# DragonUSBHost.net
KiCad netlist of a schematic drawn in EAGLE
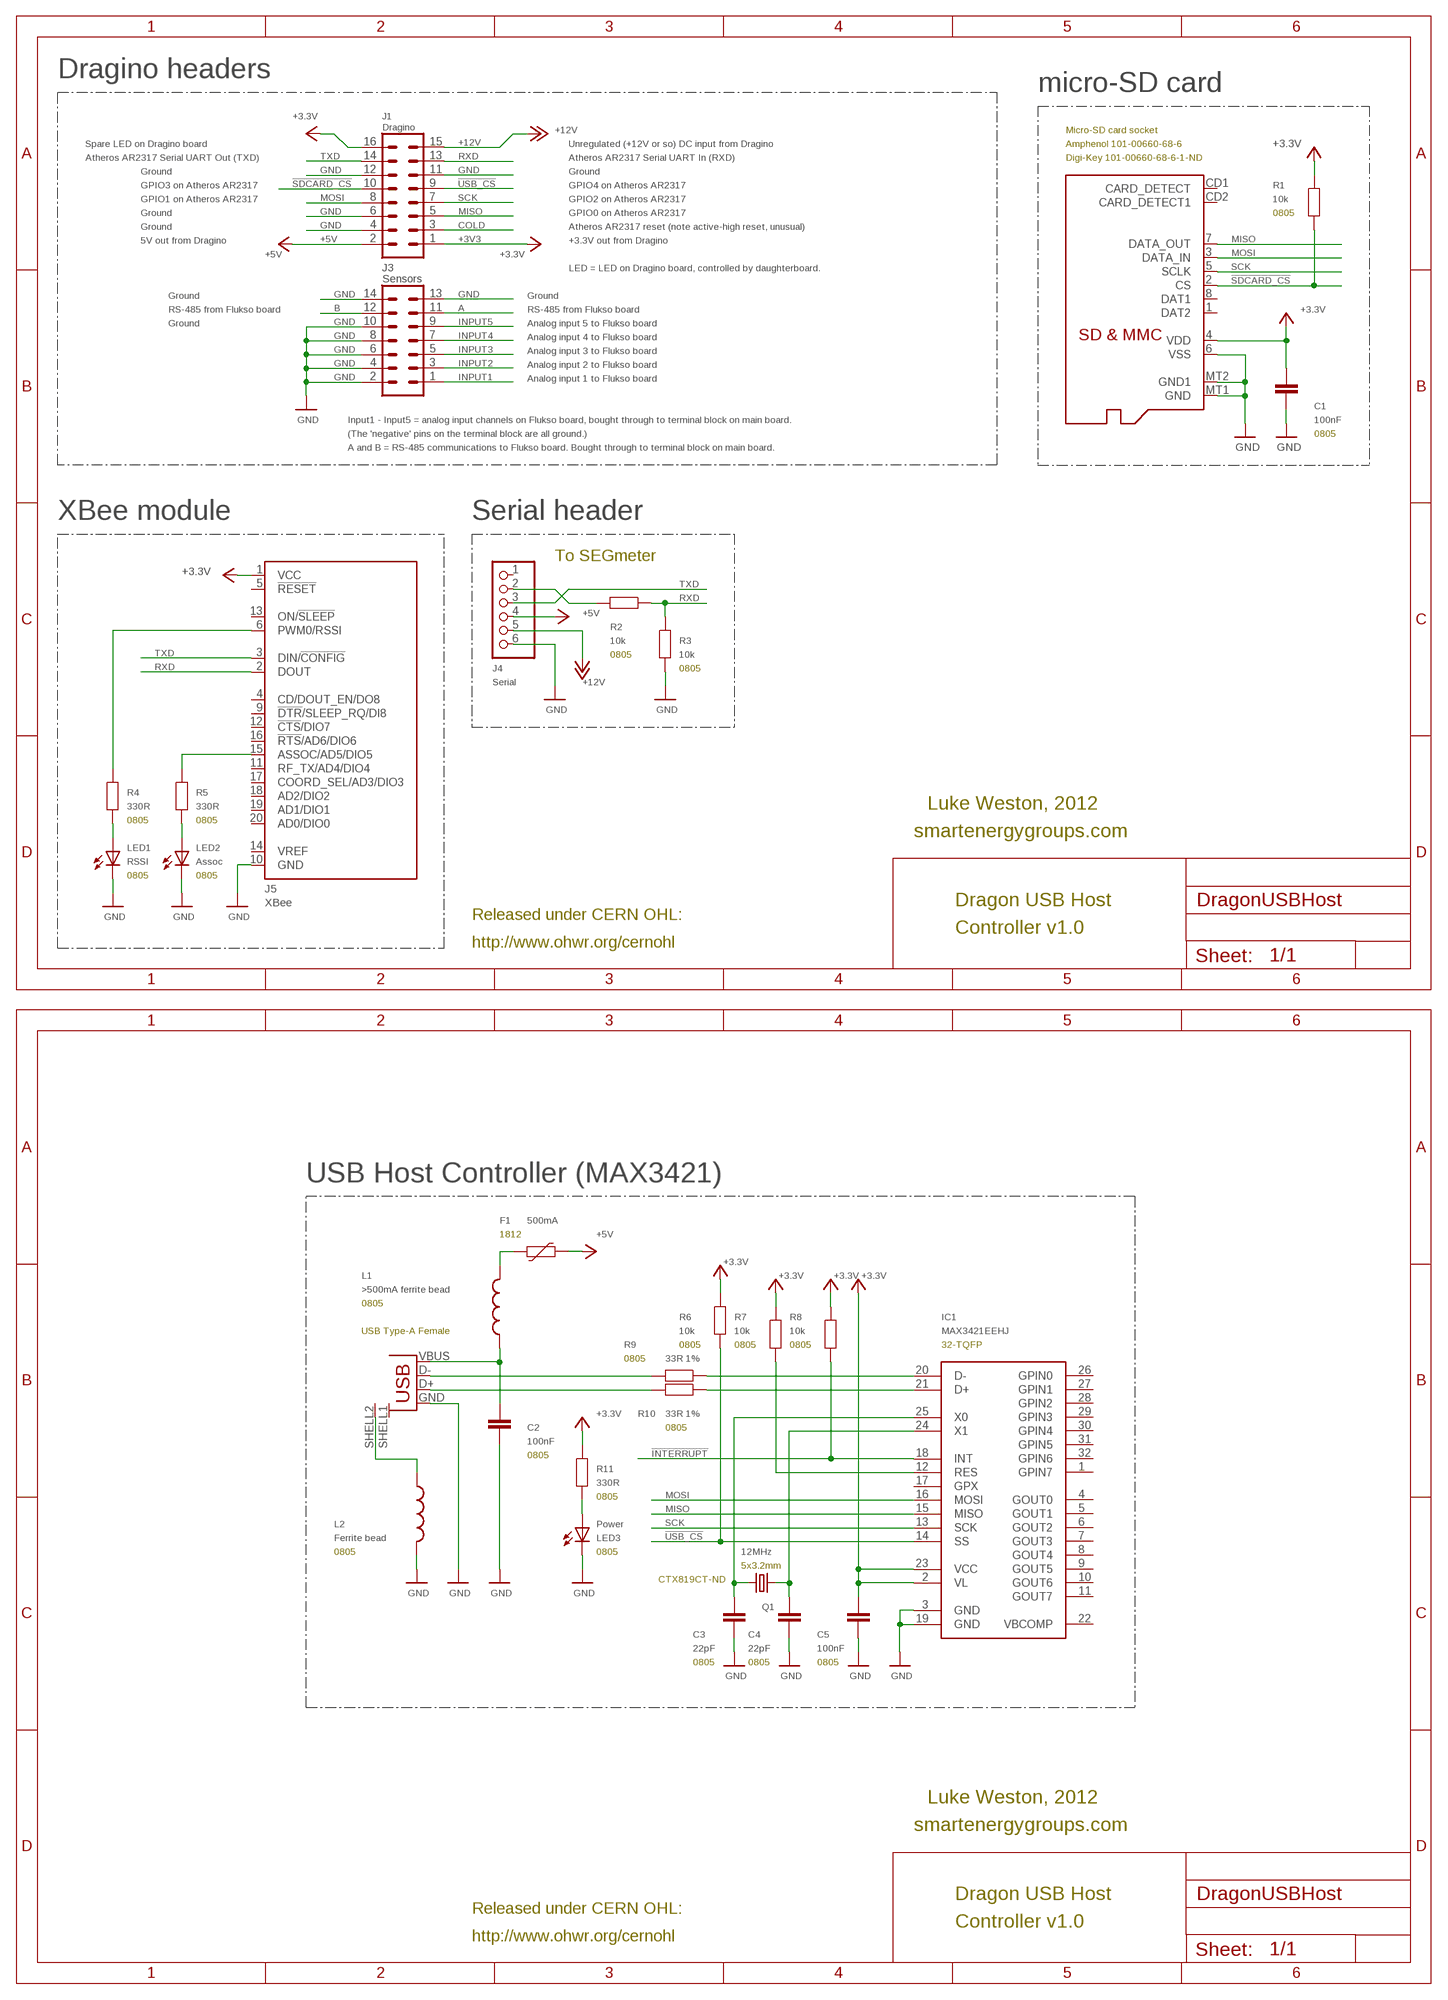
[diagram p0: schematic, sheet 1]

(export (version "E")
  (design (tool "Eeschema 10.0.6"))
  (components
    (comp (ref "C1")
      (value "100nF")
      (footprint "eagle-import:0805")
      (libsource (lib "eagle-import") (part "CAP0805"))
    )
    (comp (ref "C2")
      (value "100nF")
      (footprint "eagle-import:0805")
      (libsource (lib "eagle-import") (part "CAP0805"))
    )
    (comp (ref "C3")
      (value "22pF")
      (footprint "eagle-import:0805")
      (libsource (lib "eagle-import") (part "CAP0805"))
    )
    (comp (ref "C4")
      (value "22pF")
      (footprint "eagle-import:0805")
      (libsource (lib "eagle-import") (part "CAP0805"))
    )
    (comp (ref "C5")
      (value "100nF")
      (footprint "eagle-import:0805")
      (libsource (lib "eagle-import") (part "CAP0805"))
    )
    (comp (ref "F1")
      (value "500mA")
      (footprint "eagle-import:1812")
      (libsource (lib "eagle-import") (part "PTC"))
    )
    (comp (ref "IC1")
      (value "MAX3421EEHJ")
      (footprint "eagle-import:TQFP32-5MM")
      (libsource (lib "eagle-import") (part "MAX3421ESMD"))
    )
    (comp (ref "J1")
      (value "Dragino")
      (footprint "eagle-import:MA08-2")
      (libsource (lib "eagle-import") (part "MA08-2"))
    )
    (comp (ref "J2")
      (value "MICROSD")
      (footprint "eagle-import:MICROSD")
      (libsource (lib "eagle-import") (part "MICROSD"))
    )
    (comp (ref "J3")
      (value "Sensors")
      (footprint "eagle-import:MA07-2")
      (libsource (lib "eagle-import") (part "MA07-2"))
    )
    (comp (ref "J4")
      (value "Serial")
      (footprint "eagle-import:1X06")
      (libsource (lib "eagle-import") (part "PINHD-1X6"))
    )
    (comp (ref "J5")
      (value "XBee")
      (footprint "eagle-import:XBEE-PRO")
      (fields (field (name "MPN") "XBP24-AWI-001"))
      (libsource (lib "eagle-import") (part "XBEE-PRO"))
    )
    (comp (ref "L1")
      (value ">500mA ferrite bead")
      (footprint "eagle-import:0805-LARGE")
      (libsource (lib "eagle-import") (part "INDUCTOR0805-LARGE"))
    )
    (comp (ref "L2")
      (value "Ferrite bead")
      (footprint "eagle-import:0805-LARGE")
      (libsource (lib "eagle-import") (part "INDUCTOR0805-LARGE"))
    )
    (comp (ref "LED1")
      (value "RSSI")
      (footprint "eagle-import:LED-0805")
      (libsource (lib "eagle-import") (part "LED0805"))
    )
    (comp (ref "LED2")
      (value "Assoc")
      (footprint "eagle-import:LED-0805")
      (libsource (lib "eagle-import") (part "LED0805"))
    )
    (comp (ref "LED3")
      (value "Power")
      (footprint "eagle-import:LED-0805")
      (libsource (lib "eagle-import") (part "LED0805"))
    )
    (comp (ref "P1")
      (value "USB_")
      (footprint "eagle-import:USB-A-S-SILK-FEMALE")
      (libsource (lib "eagle-import") (part "USB_"))
    )
    (comp (ref "Q1")
      (value "12MHz")
      (footprint "eagle-import:CRYSTAL-SMD-5X3")
      (libsource (lib "eagle-import") (part "CRYSTAL5X3"))
    )
    (comp (ref "R1")
      (value "10k")
      (footprint "eagle-import:0805")
      (libsource (lib "eagle-import") (part "RESISTOR0805"))
    )
    (comp (ref "R2")
      (value "10k")
      (footprint "eagle-import:0805")
      (libsource (lib "eagle-import") (part "RESISTOR0805"))
    )
    (comp (ref "R3")
      (value "10k")
      (footprint "eagle-import:0805")
      (libsource (lib "eagle-import") (part "RESISTOR0805"))
    )
    (comp (ref "R4")
      (value "330R")
      (footprint "eagle-import:0805")
      (libsource (lib "eagle-import") (part "RESISTOR0805"))
    )
    (comp (ref "R5")
      (value "330R")
      (footprint "eagle-import:0805")
      (libsource (lib "eagle-import") (part "RESISTOR0805"))
    )
    (comp (ref "R6")
      (value "10k")
      (footprint "eagle-import:0805")
      (libsource (lib "eagle-import") (part "RESISTOR0805"))
    )
    (comp (ref "R7")
      (value "10k")
      (footprint "eagle-import:0805")
      (libsource (lib "eagle-import") (part "RESISTOR0805"))
    )
    (comp (ref "R8")
      (value "10k")
      (footprint "eagle-import:0805")
      (libsource (lib "eagle-import") (part "RESISTOR0805"))
    )
    (comp (ref "R9")
      (value "33R 1%")
      (footprint "eagle-import:0805")
      (libsource (lib "eagle-import") (part "RESISTOR0805"))
    )
    (comp (ref "R10")
      (value "33R 1%")
      (footprint "eagle-import:0805")
      (libsource (lib "eagle-import") (part "RESISTOR0805"))
    )
    (comp (ref "R11")
      (value "330R")
      (footprint "eagle-import:0805")
      (libsource (lib "eagle-import") (part "RESISTOR0805"))
    )
  )
  (nets
    (net (code "1") (name "+3.3V") (class "Default")
      (node (ref "C1") (pin "1") (pinfunction "1_1") (pintype "passive"))
      (node (ref "C5") (pin "1") (pinfunction "1_1") (pintype "passive"))
      (node (ref "IC1") (pin "2") (pinfunction "VL_2") (pintype "bidirectional"))
      (node (ref "IC1") (pin "23") (pinfunction "VCC_23") (pintype "bidirectional"))
      (node (ref "J1") (pin "1") (pinfunction "1_1") (pintype "passive"))
      (node (ref "J1") (pin "16") (pinfunction "16_16") (pintype "passive"))
      (node (ref "J2") (pin "4") (pinfunction "VDD_4") (pintype "power_in"))
      (node (ref "J5") (pin "1") (pinfunction "VCC_1") (pintype "power_in"))
      (node (ref "R1") (pin "2") (pinfunction "2_2") (pintype "passive"))
      (node (ref "R11") (pin "2") (pinfunction "2_2") (pintype "passive"))
      (node (ref "R6") (pin "2") (pinfunction "2_2") (pintype "passive"))
      (node (ref "R7") (pin "2") (pinfunction "2_2") (pintype "passive"))
      (node (ref "R8") (pin "2") (pinfunction "2_2") (pintype "passive"))
    )
    (net (code "2") (name "+5V") (class "Default")
      (node (ref "F1") (pin "2") (pinfunction "P$2_2") (pintype "bidirectional"))
      (node (ref "J1") (pin "2") (pinfunction "2_2") (pintype "passive"))
      (node (ref "J4") (pin "4") (pinfunction "4_4") (pintype "passive"))
    )
    (net (code "3") (name "+12V") (class "Default")
      (node (ref "J1") (pin "15") (pinfunction "15_15") (pintype "passive"))
      (node (ref "J4") (pin "5") (pinfunction "5_5") (pintype "passive"))
    )
    (net (code "4") (name "/A") (class "Default")
      (node (ref "J3") (pin "11") (pinfunction "11_11") (pintype "passive"))
    )
    (net (code "5") (name "/B") (class "Default")
      (node (ref "J3") (pin "12") (pinfunction "12_12") (pintype "passive"))
    )
    (net (code "6") (name "/COLD") (class "Default")
      (node (ref "J1") (pin "3") (pinfunction "3_3") (pintype "passive"))
    )
    (net (code "7") (name "/INPUT1") (class "Default")
      (node (ref "J3") (pin "1") (pinfunction "1_1") (pintype "passive"))
    )
    (net (code "8") (name "/INPUT2") (class "Default")
      (node (ref "J3") (pin "3") (pinfunction "3_3") (pintype "passive"))
    )
    (net (code "9") (name "/INPUT3") (class "Default")
      (node (ref "J3") (pin "5") (pinfunction "5_5") (pintype "passive"))
    )
    (net (code "10") (name "/INPUT4") (class "Default")
      (node (ref "J3") (pin "7") (pinfunction "7_7") (pintype "passive"))
    )
    (net (code "11") (name "/INPUT5") (class "Default")
      (node (ref "J3") (pin "9") (pinfunction "9_9") (pintype "passive"))
    )
    (net (code "12") (name "/MISO") (class "Default")
      (node (ref "IC1") (pin "15") (pinfunction "MISO_15") (pintype "bidirectional"))
      (node (ref "J1") (pin "5") (pinfunction "5_5") (pintype "passive"))
      (node (ref "J2") (pin "7") (pinfunction "DATA_OUT_7") (pintype "output"))
    )
    (net (code "13") (name "/MOSI") (class "Default")
      (node (ref "IC1") (pin "16") (pinfunction "MOSI_16") (pintype "bidirectional"))
      (node (ref "J1") (pin "8") (pinfunction "8_8") (pintype "passive"))
      (node (ref "J2") (pin "3") (pinfunction "DATA_IN_3") (pintype "input"))
    )
    (net (code "14") (name "/RXD") (class "Default")
      (node (ref "J1") (pin "13") (pinfunction "13_13") (pintype "passive"))
      (node (ref "J5") (pin "2") (pinfunction "DOUT_2") (pintype "output"))
      (node (ref "R2") (pin "1") (pinfunction "1_1") (pintype "passive"))
      (node (ref "R3") (pin "2") (pinfunction "2_2") (pintype "passive"))
    )
    (net (code "15") (name "/SCK") (class "Default")
      (node (ref "IC1") (pin "13") (pinfunction "SCK_13") (pintype "bidirectional"))
      (node (ref "J1") (pin "7") (pinfunction "7_7") (pintype "passive"))
      (node (ref "J2") (pin "5") (pinfunction "SCLK_5") (pintype "input"))
    )
    (net (code "16") (name "/TXD") (class "Default")
      (node (ref "J1") (pin "14") (pinfunction "14_14") (pintype "passive"))
      (node (ref "J4") (pin "3") (pinfunction "3_3") (pintype "passive"))
      (node (ref "J5") (pin "3") (pinfunction "DIN/~{CONFIG}_3") (pintype "input"))
    )
    (net (code "17") (name "/~{INTERRUPT}") (class "Default")
      (node (ref "IC1") (pin "18") (pinfunction "INT_18") (pintype "bidirectional"))
      (node (ref "R8") (pin "1") (pinfunction "1_1") (pintype "passive"))
    )
    (net (code "18") (name "/~{SDCARD_CS}") (class "Default")
      (node (ref "J1") (pin "10") (pinfunction "10_10") (pintype "passive"))
      (node (ref "J2") (pin "2") (pinfunction "CS_2") (pintype "input"))
      (node (ref "R1") (pin "1") (pinfunction "1_1") (pintype "passive"))
    )
    (net (code "19") (name "/~{USB_CS}") (class "Default")
      (node (ref "IC1") (pin "14") (pinfunction "SS_14") (pintype "bidirectional"))
      (node (ref "J1") (pin "9") (pinfunction "9_9") (pintype "passive"))
      (node (ref "R6") (pin "1") (pinfunction "1_1") (pintype "passive"))
    )
    (net (code "20") (name "GND") (class "Default")
      (node (ref "C1") (pin "2") (pinfunction "2_2") (pintype "passive"))
      (node (ref "C2") (pin "1") (pinfunction "1_1") (pintype "passive"))
      (node (ref "C3") (pin "2") (pinfunction "2_2") (pintype "passive"))
      (node (ref "C4") (pin "2") (pinfunction "2_2") (pintype "passive"))
      (node (ref "C5") (pin "2") (pinfunction "2_2") (pintype "passive"))
      (node (ref "IC1") (pin "19") (pinfunction "GND_19") (pintype "bidirectional"))
      (node (ref "IC1") (pin "3") (pinfunction "GND_3") (pintype "bidirectional"))
      (node (ref "J1") (pin "11") (pinfunction "11_11") (pintype "passive"))
      (node (ref "J1") (pin "12") (pinfunction "12_12") (pintype "passive"))
      (node (ref "J1") (pin "4") (pinfunction "4_4") (pintype "passive"))
      (node (ref "J1") (pin "6") (pinfunction "6_6") (pintype "passive"))
      (node (ref "J2") (pin "6") (pinfunction "VSS_6") (pintype "power_in"))
      (node (ref "J2") (pin "MT1") (pinfunction "GND_MT1") (pintype "power_in"))
      (node (ref "J2") (pin "MT2") (pinfunction "GND1_MT2") (pintype "power_in"))
      (node (ref "J3") (pin "10") (pinfunction "10_10") (pintype "passive"))
      (node (ref "J3") (pin "13") (pinfunction "13_13") (pintype "passive"))
      (node (ref "J3") (pin "14") (pinfunction "14_14") (pintype "passive"))
      (node (ref "J3") (pin "2") (pinfunction "2_2") (pintype "passive"))
      (node (ref "J3") (pin "4") (pinfunction "4_4") (pintype "passive"))
      (node (ref "J3") (pin "6") (pinfunction "6_6") (pintype "passive"))
      (node (ref "J3") (pin "8") (pinfunction "8_8") (pintype "passive"))
      (node (ref "J4") (pin "6") (pinfunction "6_6") (pintype "passive"))
      (node (ref "J5") (pin "10") (pinfunction "GND_10") (pintype "power_in"))
      (node (ref "L2") (pin "2") (pinfunction "2_2") (pintype "passive"))
      (node (ref "LED1") (pin "C") (pinfunction "C_C") (pintype "passive"))
      (node (ref "LED2") (pin "C") (pinfunction "C_C") (pintype "passive"))
      (node (ref "LED3") (pin "C") (pinfunction "C_C") (pintype "passive"))
      (node (ref "P1") (pin "GND") (pinfunction "GND_GND") (pintype "bidirectional"))
      (node (ref "R3") (pin "1") (pinfunction "1_1") (pintype "passive"))
    )
    (net (code "21") (name "Net-(C2-Pad2)") (class "Default")
      (node (ref "C2") (pin "2") (pinfunction "2_2") (pintype "passive"))
      (node (ref "L1") (pin "1") (pinfunction "1_1") (pintype "passive"))
      (node (ref "P1") (pin "VBUS") (pinfunction "VBUS_VBUS") (pintype "bidirectional"))
    )
    (net (code "22") (name "Net-(F1-P$1)") (class "Default")
      (node (ref "F1") (pin "1") (pinfunction "P$1_1") (pintype "bidirectional"))
      (node (ref "L1") (pin "2") (pinfunction "2_2") (pintype "passive"))
    )
    (net (code "23") (name "Net-(IC1-D+)") (class "Default")
      (node (ref "IC1") (pin "21") (pinfunction "D+_21") (pintype "bidirectional"))
      (node (ref "R10") (pin "1") (pinfunction "1_1") (pintype "passive"))
    )
    (net (code "24") (name "Net-(IC1-D-)") (class "Default")
      (node (ref "IC1") (pin "20") (pinfunction "D-_20") (pintype "bidirectional"))
      (node (ref "R9") (pin "1") (pinfunction "1_1") (pintype "passive"))
    )
    (net (code "25") (name "Net-(IC1-RES)") (class "Default")
      (node (ref "IC1") (pin "12") (pinfunction "RES_12") (pintype "bidirectional"))
      (node (ref "R7") (pin "1") (pinfunction "1_1") (pintype "passive"))
    )
    (net (code "26") (name "Net-(IC1-X0)") (class "Default")
      (node (ref "C3") (pin "1") (pinfunction "1_1") (pintype "passive"))
      (node (ref "IC1") (pin "25") (pinfunction "X0_25") (pintype "bidirectional"))
      (node (ref "Q1") (pin "3") (pinfunction "2_3") (pintype "passive"))
    )
    (net (code "27") (name "Net-(IC1-X1)") (class "Default")
      (node (ref "C4") (pin "1") (pinfunction "1_1") (pintype "passive"))
      (node (ref "IC1") (pin "24") (pinfunction "X1_24") (pintype "bidirectional"))
      (node (ref "Q1") (pin "1") (pinfunction "1_1") (pintype "passive"))
    )
    (net (code "28") (name "Net-(J4-Pad2)") (class "Default")
      (node (ref "J4") (pin "2") (pinfunction "2_2") (pintype "passive"))
      (node (ref "R2") (pin "2") (pinfunction "2_2") (pintype "passive"))
    )
    (net (code "29") (name "Net-(J5-ASSOC{slash}AD5{slash}DIO5)") (class "Default")
      (node (ref "J5") (pin "15") (pinfunction "ASSOC/AD5/DIO5_15") (pintype "bidirectional"))
      (node (ref "R5") (pin "2") (pinfunction "2_2") (pintype "passive"))
    )
    (net (code "30") (name "Net-(J5-PWM0{slash}RSSI)") (class "Default")
      (node (ref "J5") (pin "6") (pinfunction "PWM0/RSSI_6") (pintype "output"))
      (node (ref "R4") (pin "2") (pinfunction "2_2") (pintype "passive"))
    )
    (net (code "31") (name "Net-(L2-Pad1)") (class "Default")
      (node (ref "L2") (pin "1") (pinfunction "1_1") (pintype "passive"))
      (node (ref "P1") (pin "SHELL2") (pinfunction "SHELL2_SHELL2") (pintype "passive"))
    )
    (net (code "32") (name "Net-(LED1-PadA)") (class "Default")
      (node (ref "LED1") (pin "A") (pinfunction "A_A") (pintype "passive"))
      (node (ref "R4") (pin "1") (pinfunction "1_1") (pintype "passive"))
    )
    (net (code "33") (name "Net-(LED2-PadA)") (class "Default")
      (node (ref "LED2") (pin "A") (pinfunction "A_A") (pintype "passive"))
      (node (ref "R5") (pin "1") (pinfunction "1_1") (pintype "passive"))
    )
    (net (code "34") (name "Net-(LED3-PadA)") (class "Default")
      (node (ref "LED3") (pin "A") (pinfunction "A_A") (pintype "passive"))
      (node (ref "R11") (pin "1") (pinfunction "1_1") (pintype "passive"))
    )
    (net (code "35") (name "Net-(P1-PadD+)") (class "Default")
      (node (ref "P1") (pin "D+") (pinfunction "D+_D+") (pintype "bidirectional"))
      (node (ref "R10") (pin "2") (pinfunction "2_2") (pintype "passive"))
    )
    (net (code "36") (name "Net-(P1-PadD-)") (class "Default")
      (node (ref "P1") (pin "D-") (pinfunction "D-_D-") (pintype "bidirectional"))
      (node (ref "R9") (pin "2") (pinfunction "2_2") (pintype "passive"))
    )
    (net (code "37") (name "unconnected-(IC1-GOUT0-Pad4)") (class "Default")
      (node (ref "IC1") (pin "4") (pinfunction "GOUT0_4") (pintype "bidirectional"))
    )
    (net (code "38") (name "unconnected-(IC1-GOUT1-Pad5)") (class "Default")
      (node (ref "IC1") (pin "5") (pinfunction "GOUT1_5") (pintype "bidirectional"))
    )
    (net (code "39") (name "unconnected-(IC1-GOUT2-Pad6)") (class "Default")
      (node (ref "IC1") (pin "6") (pinfunction "GOUT2_6") (pintype "bidirectional"))
    )
    (net (code "40") (name "unconnected-(IC1-GOUT3-Pad7)") (class "Default")
      (node (ref "IC1") (pin "7") (pinfunction "GOUT3_7") (pintype "bidirectional"))
    )
    (net (code "41") (name "unconnected-(IC1-GOUT4-Pad8)") (class "Default")
      (node (ref "IC1") (pin "8") (pinfunction "GOUT4_8") (pintype "bidirectional"))
    )
    (net (code "42") (name "unconnected-(IC1-GOUT5-Pad9)") (class "Default")
      (node (ref "IC1") (pin "9") (pinfunction "GOUT5_9") (pintype "bidirectional"))
    )
    (net (code "43") (name "unconnected-(IC1-GOUT6-Pad10)") (class "Default")
      (node (ref "IC1") (pin "10") (pinfunction "GOUT6_10") (pintype "bidirectional"))
    )
    (net (code "44") (name "unconnected-(IC1-GOUT7-Pad11)") (class "Default")
      (node (ref "IC1") (pin "11") (pinfunction "GOUT7_11") (pintype "bidirectional"))
    )
    (net (code "45") (name "unconnected-(IC1-GPIN0-Pad26)") (class "Default")
      (node (ref "IC1") (pin "26") (pinfunction "GPIN0_26") (pintype "bidirectional"))
    )
    (net (code "46") (name "unconnected-(IC1-GPIN1-Pad27)") (class "Default")
      (node (ref "IC1") (pin "27") (pinfunction "GPIN1_27") (pintype "bidirectional"))
    )
    (net (code "47") (name "unconnected-(IC1-GPIN2-Pad28)") (class "Default")
      (node (ref "IC1") (pin "28") (pinfunction "GPIN2_28") (pintype "bidirectional"))
    )
    (net (code "48") (name "unconnected-(IC1-GPIN3-Pad29)") (class "Default")
      (node (ref "IC1") (pin "29") (pinfunction "GPIN3_29") (pintype "bidirectional"))
    )
    (net (code "49") (name "unconnected-(IC1-GPIN4-Pad30)") (class "Default")
      (node (ref "IC1") (pin "30") (pinfunction "GPIN4_30") (pintype "bidirectional"))
    )
    (net (code "50") (name "unconnected-(IC1-GPIN5-Pad31)") (class "Default")
      (node (ref "IC1") (pin "31") (pinfunction "GPIN5_31") (pintype "bidirectional"))
    )
    (net (code "51") (name "unconnected-(IC1-GPIN6-Pad32)") (class "Default")
      (node (ref "IC1") (pin "32") (pinfunction "GPIN6_32") (pintype "bidirectional"))
    )
    (net (code "52") (name "unconnected-(IC1-GPIN7-Pad1)") (class "Default")
      (node (ref "IC1") (pin "1") (pinfunction "GPIN7_1") (pintype "bidirectional"))
    )
    (net (code "53") (name "unconnected-(IC1-GPX-Pad17)") (class "Default")
      (node (ref "IC1") (pin "17") (pinfunction "GPX_17") (pintype "bidirectional"))
    )
    (net (code "54") (name "unconnected-(IC1-VBCOMP-Pad22)") (class "Default")
      (node (ref "IC1") (pin "22") (pinfunction "VBCOMP_22") (pintype "bidirectional"))
    )
    (net (code "55") (name "unconnected-(J2-CARD_DETECT-PadCD1)") (class "Default")
      (node (ref "J2") (pin "CD1") (pinfunction "CARD_DETECT_CD1") (pintype "passive"))
    )
    (net (code "56") (name "unconnected-(J2-CARD_DETECT1-PadCD2)") (class "Default")
      (node (ref "J2") (pin "CD2") (pinfunction "CARD_DETECT1_CD2") (pintype "passive"))
    )
    (net (code "57") (name "unconnected-(J2-DAT1-Pad8)") (class "Default")
      (node (ref "J2") (pin "8") (pinfunction "DAT1_8") (pintype "bidirectional"))
    )
    (net (code "58") (name "unconnected-(J2-DAT2-Pad1)") (class "Default")
      (node (ref "J2") (pin "1") (pinfunction "DAT2_1") (pintype "bidirectional"))
    )
    (net (code "59") (name "unconnected-(J4-Pad1)") (class "Default")
      (node (ref "J4") (pin "1") (pinfunction "1_1") (pintype "passive"))
    )
    (net (code "60") (name "unconnected-(J5-AD0{slash}DIO0-Pad20)") (class "Default")
      (node (ref "J5") (pin "20") (pinfunction "AD0/DIO0_20") (pintype "bidirectional"))
    )
    (net (code "61") (name "unconnected-(J5-AD1{slash}DIO1-Pad19)") (class "Default")
      (node (ref "J5") (pin "19") (pinfunction "AD1/DIO1_19") (pintype "bidirectional"))
    )
    (net (code "62") (name "unconnected-(J5-AD2{slash}DIO2-Pad18)") (class "Default")
      (node (ref "J5") (pin "18") (pinfunction "AD2/DIO2_18") (pintype "bidirectional"))
    )
    (net (code "63") (name "unconnected-(J5-CD{slash}DOUT_EN{slash}DO8-Pad4)") (class "Default")
      (node (ref "J5") (pin "4") (pinfunction "CD/DOUT_EN/DO8_4") (pintype "output"))
    )
    (net (code "64") (name "unconnected-(J5-COORD_SEL{slash}AD3{slash}DIO3-Pad17)") (class "Default")
      (node (ref "J5") (pin "17") (pinfunction "COORD_SEL/AD3/DIO3_17") (pintype "bidirectional"))
    )
    (net (code "65") (name "unconnected-(J5-ON{slash}~{SLEEP}-Pad13)") (class "Default")
      (node (ref "J5") (pin "13") (pinfunction "ON/~{SLEEP}_13") (pintype "output"))
    )
    (net (code "66") (name "unconnected-(J5-RF_TX{slash}AD4{slash}DIO4-Pad11)") (class "Default")
      (node (ref "J5") (pin "11") (pinfunction "RF_TX/AD4/DIO4_11") (pintype "bidirectional"))
    )
    (net (code "67") (name "unconnected-(J5-VREF-Pad14)") (class "Default")
      (node (ref "J5") (pin "14") (pinfunction "VREF_14") (pintype "input"))
    )
    (net (code "68") (name "unconnected-(J5-~{CTS}{slash}DIO7-Pad12)") (class "Default")
      (node (ref "J5") (pin "12") (pinfunction "~{CTS}/DIO7_12") (pintype "bidirectional"))
    )
    (net (code "69") (name "unconnected-(J5-~{DTR}{slash}SLEEP_RQ{slash}DI8-Pad9)") (class "Default")
      (node (ref "J5") (pin "9") (pinfunction "~{DTR}/SLEEP_RQ/DI8_9") (pintype "bidirectional"))
    )
    (net (code "70") (name "unconnected-(J5-~{RESET}-Pad5)") (class "Default")
      (node (ref "J5") (pin "5") (pinfunction "~{RESET}_5") (pintype "input"))
    )
    (net (code "71") (name "unconnected-(J5-~{RTS}{slash}AD6{slash}DIO6-Pad16)") (class "Default")
      (node (ref "J5") (pin "16") (pinfunction "~{RTS}/AD6/DIO6_16") (pintype "bidirectional"))
    )
    (net (code "72") (name "unconnected-(P1-PadSHELL1)") (class "Default")
      (node (ref "P1") (pin "SHELL1") (pinfunction "SHELL1_SHELL1") (pintype "passive"))
    )
  )
)
